# MicroWordClock2.net
KiCad netlist of a schematic drawn in EAGLE
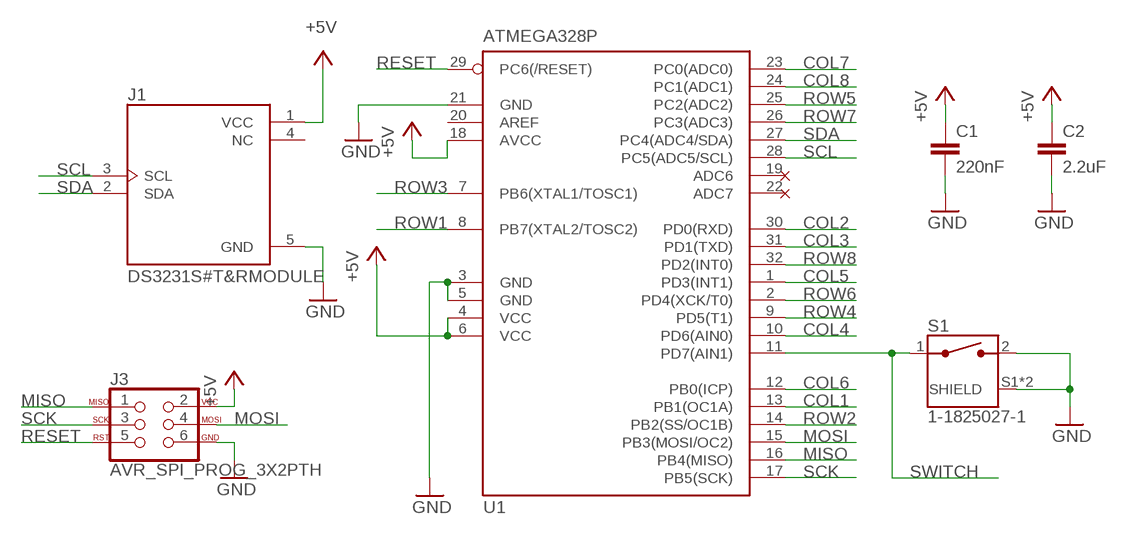
[diagram p0: schematic, sheet 1]
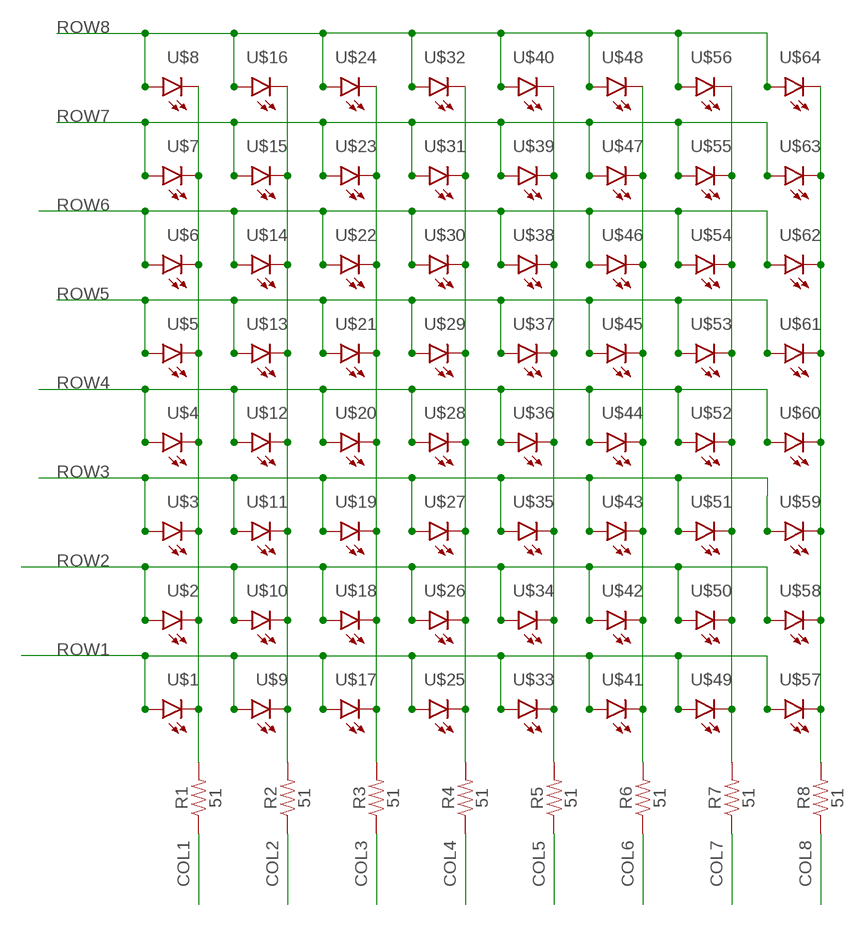
[diagram p1: schematic, sheet 2]
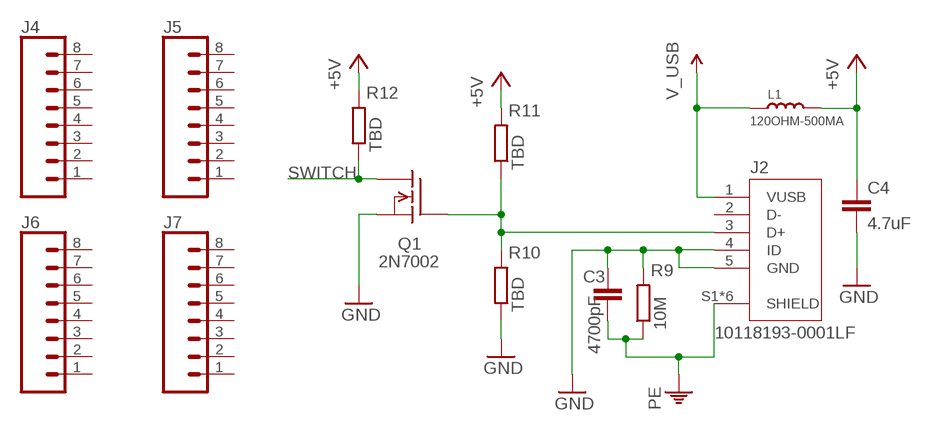
[diagram p2: schematic, sheet 3]

(export (version "E")
  (design (tool "Eeschema 10.0.6"))
  (components
    (comp (ref "R1")
      (value "51")
      (footprint "eagle-import:0603")
      (libsource (lib "eagle-import") (part "470OHM-0603-1/10W-1%"))
    )
    (comp (ref "R2")
      (value "51")
      (footprint "eagle-import:0603")
      (libsource (lib "eagle-import") (part "470OHM-0603-1/10W-1%"))
    )
    (comp (ref "R3")
      (value "51")
      (footprint "eagle-import:0603")
      (libsource (lib "eagle-import") (part "470OHM-0603-1/10W-1%"))
    )
    (comp (ref "R4")
      (value "51")
      (footprint "eagle-import:0603")
      (libsource (lib "eagle-import") (part "470OHM-0603-1/10W-1%"))
    )
    (comp (ref "R5")
      (value "51")
      (footprint "eagle-import:0603")
      (libsource (lib "eagle-import") (part "470OHM-0603-1/10W-1%"))
    )
    (comp (ref "R6")
      (value "51")
      (footprint "eagle-import:0603")
      (libsource (lib "eagle-import") (part "470OHM-0603-1/10W-1%"))
    )
    (comp (ref "R7")
      (value "51")
      (footprint "eagle-import:0603")
      (libsource (lib "eagle-import") (part "470OHM-0603-1/10W-1%"))
    )
    (comp (ref "R8")
      (value "51")
      (footprint "eagle-import:0603")
      (libsource (lib "eagle-import") (part "470OHM-0603-1/10W-1%"))
    )
    (comp (ref "U$1")
      (value "WHITE")
      (footprint "eagle-import:1113(2835METRIC)")
      (libsource (lib "eagle-import") (part "JE2835AWT-00-0000-0B0A0BG840E"))
    )
    (comp (ref "U$2")
      (value "WHITE")
      (footprint "eagle-import:1113(2835METRIC)")
      (libsource (lib "eagle-import") (part "JE2835AWT-00-0000-0B0A0BG840E"))
    )
    (comp (ref "U$3")
      (value "WHITE")
      (footprint "eagle-import:1113(2835METRIC)")
      (libsource (lib "eagle-import") (part "JE2835AWT-00-0000-0B0A0BG840E"))
    )
    (comp (ref "U$4")
      (value "WHITE")
      (footprint "eagle-import:1113(2835METRIC)")
      (libsource (lib "eagle-import") (part "JE2835AWT-00-0000-0B0A0BG840E"))
    )
    (comp (ref "U$5")
      (value "WHITE")
      (footprint "eagle-import:1113(2835METRIC)")
      (libsource (lib "eagle-import") (part "JE2835AWT-00-0000-0B0A0BG840E"))
    )
    (comp (ref "U$6")
      (value "WHITE")
      (footprint "eagle-import:1113(2835METRIC)")
      (libsource (lib "eagle-import") (part "JE2835AWT-00-0000-0B0A0BG840E"))
    )
    (comp (ref "U$7")
      (value "WHITE")
      (footprint "eagle-import:1113(2835METRIC)")
      (libsource (lib "eagle-import") (part "JE2835AWT-00-0000-0B0A0BG840E"))
    )
    (comp (ref "U$8")
      (value "WHITE")
      (footprint "eagle-import:1113(2835METRIC)")
      (libsource (lib "eagle-import") (part "JE2835AWT-00-0000-0B0A0BG840E"))
    )
    (comp (ref "U$9")
      (value "WHITE")
      (footprint "eagle-import:1113(2835METRIC)")
      (libsource (lib "eagle-import") (part "JE2835AWT-00-0000-0B0A0BG840E"))
    )
    (comp (ref "U$10")
      (value "WHITE")
      (footprint "eagle-import:1113(2835METRIC)")
      (libsource (lib "eagle-import") (part "JE2835AWT-00-0000-0B0A0BG840E"))
    )
    (comp (ref "U$11")
      (value "WHITE")
      (footprint "eagle-import:1113(2835METRIC)")
      (libsource (lib "eagle-import") (part "JE2835AWT-00-0000-0B0A0BG840E"))
    )
    (comp (ref "U$12")
      (value "WHITE")
      (footprint "eagle-import:1113(2835METRIC)")
      (libsource (lib "eagle-import") (part "JE2835AWT-00-0000-0B0A0BG840E"))
    )
    (comp (ref "U$13")
      (value "WHITE")
      (footprint "eagle-import:1113(2835METRIC)")
      (libsource (lib "eagle-import") (part "JE2835AWT-00-0000-0B0A0BG840E"))
    )
    (comp (ref "U$14")
      (value "WHITE")
      (footprint "eagle-import:1113(2835METRIC)")
      (libsource (lib "eagle-import") (part "JE2835AWT-00-0000-0B0A0BG840E"))
    )
    (comp (ref "U$15")
      (value "WHITE")
      (footprint "eagle-import:1113(2835METRIC)")
      (libsource (lib "eagle-import") (part "JE2835AWT-00-0000-0B0A0BG840E"))
    )
    (comp (ref "U$16")
      (value "WHITE")
      (footprint "eagle-import:1113(2835METRIC)")
      (libsource (lib "eagle-import") (part "JE2835AWT-00-0000-0B0A0BG840E"))
    )
    (comp (ref "U$17")
      (value "WHITE")
      (footprint "eagle-import:1113(2835METRIC)")
      (libsource (lib "eagle-import") (part "JE2835AWT-00-0000-0B0A0BG840E"))
    )
    (comp (ref "U$18")
      (value "WHITE")
      (footprint "eagle-import:1113(2835METRIC)")
      (libsource (lib "eagle-import") (part "JE2835AWT-00-0000-0B0A0BG840E"))
    )
    (comp (ref "U$19")
      (value "WHITE")
      (footprint "eagle-import:1113(2835METRIC)")
      (libsource (lib "eagle-import") (part "JE2835AWT-00-0000-0B0A0BG840E"))
    )
    (comp (ref "U$20")
      (value "WHITE")
      (footprint "eagle-import:1113(2835METRIC)")
      (libsource (lib "eagle-import") (part "JE2835AWT-00-0000-0B0A0BG840E"))
    )
    (comp (ref "U$21")
      (value "WHITE")
      (footprint "eagle-import:1113(2835METRIC)")
      (libsource (lib "eagle-import") (part "JE2835AWT-00-0000-0B0A0BG840E"))
    )
    (comp (ref "U$22")
      (value "WHITE")
      (footprint "eagle-import:1113(2835METRIC)")
      (libsource (lib "eagle-import") (part "JE2835AWT-00-0000-0B0A0BG840E"))
    )
    (comp (ref "U$23")
      (value "WHITE")
      (footprint "eagle-import:1113(2835METRIC)")
      (libsource (lib "eagle-import") (part "JE2835AWT-00-0000-0B0A0BG840E"))
    )
    (comp (ref "U$24")
      (value "WHITE")
      (footprint "eagle-import:1113(2835METRIC)")
      (libsource (lib "eagle-import") (part "JE2835AWT-00-0000-0B0A0BG840E"))
    )
    (comp (ref "U$25")
      (value "WHITE")
      (footprint "eagle-import:1113(2835METRIC)")
      (libsource (lib "eagle-import") (part "JE2835AWT-00-0000-0B0A0BG840E"))
    )
    (comp (ref "U$26")
      (value "WHITE")
      (footprint "eagle-import:1113(2835METRIC)")
      (libsource (lib "eagle-import") (part "JE2835AWT-00-0000-0B0A0BG840E"))
    )
    (comp (ref "U$27")
      (value "WHITE")
      (footprint "eagle-import:1113(2835METRIC)")
      (libsource (lib "eagle-import") (part "JE2835AWT-00-0000-0B0A0BG840E"))
    )
    (comp (ref "U$28")
      (value "WHITE")
      (footprint "eagle-import:1113(2835METRIC)")
      (libsource (lib "eagle-import") (part "JE2835AWT-00-0000-0B0A0BG840E"))
    )
    (comp (ref "U$29")
      (value "WHITE")
      (footprint "eagle-import:1113(2835METRIC)")
      (libsource (lib "eagle-import") (part "JE2835AWT-00-0000-0B0A0BG840E"))
    )
    (comp (ref "U$30")
      (value "WHITE")
      (footprint "eagle-import:1113(2835METRIC)")
      (libsource (lib "eagle-import") (part "JE2835AWT-00-0000-0B0A0BG840E"))
    )
    (comp (ref "U$31")
      (value "WHITE")
      (footprint "eagle-import:1113(2835METRIC)")
      (libsource (lib "eagle-import") (part "JE2835AWT-00-0000-0B0A0BG840E"))
    )
    (comp (ref "U$32")
      (value "WHITE")
      (footprint "eagle-import:1113(2835METRIC)")
      (libsource (lib "eagle-import") (part "JE2835AWT-00-0000-0B0A0BG840E"))
    )
    (comp (ref "U$33")
      (value "WHITE")
      (footprint "eagle-import:1113(2835METRIC)")
      (libsource (lib "eagle-import") (part "JE2835AWT-00-0000-0B0A0BG840E"))
    )
    (comp (ref "U$34")
      (value "WHITE")
      (footprint "eagle-import:1113(2835METRIC)")
      (libsource (lib "eagle-import") (part "JE2835AWT-00-0000-0B0A0BG840E"))
    )
    (comp (ref "U$35")
      (value "WHITE")
      (footprint "eagle-import:1113(2835METRIC)")
      (libsource (lib "eagle-import") (part "JE2835AWT-00-0000-0B0A0BG840E"))
    )
    (comp (ref "U$36")
      (value "WHITE")
      (footprint "eagle-import:1113(2835METRIC)")
      (libsource (lib "eagle-import") (part "JE2835AWT-00-0000-0B0A0BG840E"))
    )
    (comp (ref "U$37")
      (value "WHITE")
      (footprint "eagle-import:1113(2835METRIC)")
      (libsource (lib "eagle-import") (part "JE2835AWT-00-0000-0B0A0BG840E"))
    )
    (comp (ref "U$38")
      (value "WHITE")
      (footprint "eagle-import:1113(2835METRIC)")
      (libsource (lib "eagle-import") (part "JE2835AWT-00-0000-0B0A0BG840E"))
    )
    (comp (ref "U$39")
      (value "WHITE")
      (footprint "eagle-import:1113(2835METRIC)")
      (libsource (lib "eagle-import") (part "JE2835AWT-00-0000-0B0A0BG840E"))
    )
    (comp (ref "U$40")
      (value "WHITE")
      (footprint "eagle-import:1113(2835METRIC)")
      (libsource (lib "eagle-import") (part "JE2835AWT-00-0000-0B0A0BG840E"))
    )
    (comp (ref "U$41")
      (value "WHITE")
      (footprint "eagle-import:1113(2835METRIC)")
      (libsource (lib "eagle-import") (part "JE2835AWT-00-0000-0B0A0BG840E"))
    )
    (comp (ref "U$42")
      (value "WHITE")
      (footprint "eagle-import:1113(2835METRIC)")
      (libsource (lib "eagle-import") (part "JE2835AWT-00-0000-0B0A0BG840E"))
    )
    (comp (ref "U$43")
      (value "WHITE")
      (footprint "eagle-import:1113(2835METRIC)")
      (libsource (lib "eagle-import") (part "JE2835AWT-00-0000-0B0A0BG840E"))
    )
    (comp (ref "U$44")
      (value "WHITE")
      (footprint "eagle-import:1113(2835METRIC)")
      (libsource (lib "eagle-import") (part "JE2835AWT-00-0000-0B0A0BG840E"))
    )
    (comp (ref "U$45")
      (value "WHITE")
      (footprint "eagle-import:1113(2835METRIC)")
      (libsource (lib "eagle-import") (part "JE2835AWT-00-0000-0B0A0BG840E"))
    )
    (comp (ref "U$46")
      (value "WHITE")
      (footprint "eagle-import:1113(2835METRIC)")
      (libsource (lib "eagle-import") (part "JE2835AWT-00-0000-0B0A0BG840E"))
    )
    (comp (ref "U$47")
      (value "WHITE")
      (footprint "eagle-import:1113(2835METRIC)")
      (libsource (lib "eagle-import") (part "JE2835AWT-00-0000-0B0A0BG840E"))
    )
    (comp (ref "U$48")
      (value "WHITE")
      (footprint "eagle-import:1113(2835METRIC)")
      (libsource (lib "eagle-import") (part "JE2835AWT-00-0000-0B0A0BG840E"))
    )
    (comp (ref "U$49")
      (value "WHITE")
      (footprint "eagle-import:1113(2835METRIC)")
      (libsource (lib "eagle-import") (part "JE2835AWT-00-0000-0B0A0BG840E"))
    )
    (comp (ref "U$50")
      (value "WHITE")
      (footprint "eagle-import:1113(2835METRIC)")
      (libsource (lib "eagle-import") (part "JE2835AWT-00-0000-0B0A0BG840E"))
    )
    (comp (ref "U$51")
      (value "WHITE")
      (footprint "eagle-import:1113(2835METRIC)")
      (libsource (lib "eagle-import") (part "JE2835AWT-00-0000-0B0A0BG840E"))
    )
    (comp (ref "U$52")
      (value "WHITE")
      (footprint "eagle-import:1113(2835METRIC)")
      (libsource (lib "eagle-import") (part "JE2835AWT-00-0000-0B0A0BG840E"))
    )
    (comp (ref "U$53")
      (value "WHITE")
      (footprint "eagle-import:1113(2835METRIC)")
      (libsource (lib "eagle-import") (part "JE2835AWT-00-0000-0B0A0BG840E"))
    )
    (comp (ref "U$54")
      (value "WHITE")
      (footprint "eagle-import:1113(2835METRIC)")
      (libsource (lib "eagle-import") (part "JE2835AWT-00-0000-0B0A0BG840E"))
    )
    (comp (ref "U$55")
      (value "WHITE")
      (footprint "eagle-import:1113(2835METRIC)")
      (libsource (lib "eagle-import") (part "JE2835AWT-00-0000-0B0A0BG840E"))
    )
    (comp (ref "U$56")
      (value "WHITE")
      (footprint "eagle-import:1113(2835METRIC)")
      (libsource (lib "eagle-import") (part "JE2835AWT-00-0000-0B0A0BG840E"))
    )
    (comp (ref "U$57")
      (value "WHITE")
      (footprint "eagle-import:1113(2835METRIC)")
      (libsource (lib "eagle-import") (part "JE2835AWT-00-0000-0B0A0BG840E"))
    )
    (comp (ref "U$58")
      (value "WHITE")
      (footprint "eagle-import:1113(2835METRIC)")
      (libsource (lib "eagle-import") (part "JE2835AWT-00-0000-0B0A0BG840E"))
    )
    (comp (ref "U$59")
      (value "WHITE")
      (footprint "eagle-import:1113(2835METRIC)")
      (libsource (lib "eagle-import") (part "JE2835AWT-00-0000-0B0A0BG840E"))
    )
    (comp (ref "U$60")
      (value "WHITE")
      (footprint "eagle-import:1113(2835METRIC)")
      (libsource (lib "eagle-import") (part "JE2835AWT-00-0000-0B0A0BG840E"))
    )
    (comp (ref "U$61")
      (value "WHITE")
      (footprint "eagle-import:1113(2835METRIC)")
      (libsource (lib "eagle-import") (part "JE2835AWT-00-0000-0B0A0BG840E"))
    )
    (comp (ref "U$62")
      (value "WHITE")
      (footprint "eagle-import:1113(2835METRIC)")
      (libsource (lib "eagle-import") (part "JE2835AWT-00-0000-0B0A0BG840E"))
    )
    (comp (ref "U$63")
      (value "WHITE")
      (footprint "eagle-import:1113(2835METRIC)")
      (libsource (lib "eagle-import") (part "JE2835AWT-00-0000-0B0A0BG840E"))
    )
    (comp (ref "U$64")
      (value "WHITE")
      (footprint "eagle-import:1113(2835METRIC)")
      (libsource (lib "eagle-import") (part "JE2835AWT-00-0000-0B0A0BG840E"))
    )
    (comp (ref "C3")
      (value "4700pF")
      (footprint "eagle-import:C0603")
      (libsource (lib "eagle-import") (part "C-EUC0603"))
    )
    (comp (ref "C4")
      (value "4.7uF")
      (footprint "eagle-import:C0603")
      (libsource (lib "eagle-import") (part "C-EUC0603"))
    )
    (comp (ref "J2")
      (value "10118193-0001LF")
      (footprint "eagle-import:FCI_10118193-0001LF")
      (fields (field (name "DIGI-KEY_PART_NUMBER") "609-4616-1-ND") (field (name "MF") "Amphenol ICC"))
      (libsource (lib "eagle-import") (part "10118193-0001LF"))
    )
    (comp (ref "J4")
      (value "CONN_08\"")
      (footprint "eagle-import:1X08")
      (libsource (lib "eagle-import") (part "CONN_08{dblquote}"))
    )
    (comp (ref "J5")
      (value "CONN_08\"")
      (footprint "eagle-import:1X08")
      (libsource (lib "eagle-import") (part "CONN_08{dblquote}"))
    )
    (comp (ref "J6")
      (value "CONN_08\"")
      (footprint "eagle-import:1X08")
      (libsource (lib "eagle-import") (part "CONN_08{dblquote}"))
    )
    (comp (ref "J7")
      (value "CONN_08\"")
      (footprint "eagle-import:1X08")
      (libsource (lib "eagle-import") (part "CONN_08{dblquote}"))
    )
    (comp (ref "L1")
      (value "120OHM-500MA")
      (footprint "eagle-import:L0603")
      (fields (field (name "MPN") "BLM18AG121SN1D"))
      (libsource (lib "eagle-import") (part "SMD-FERRITE-CHIP-120-OHM-500MA(0603)"))
    )
    (comp (ref "Q1")
      (value "2N7002")
      (footprint "eagle-import:SOT23")
      (fields (field (name "MF") "STMicroelectronics"))
      (libsource (lib "eagle-import") (part "2N7002"))
    )
    (comp (ref "R9")
      (value "10M")
      (footprint "eagle-import:R0603")
      (libsource (lib "eagle-import") (part "R-EU_R0603"))
    )
    (comp (ref "R10")
      (value "TBD")
      (footprint "eagle-import:R0603")
      (libsource (lib "eagle-import") (part "R-EU_R0603"))
    )
    (comp (ref "R11")
      (value "TBD")
      (footprint "eagle-import:R0603")
      (libsource (lib "eagle-import") (part "R-EU_R0603"))
    )
    (comp (ref "R12")
      (value "TBD")
      (footprint "eagle-import:R0603")
      (libsource (lib "eagle-import") (part "R-EU_R0603"))
    )
    (comp (ref "C1")
      (value "220nF")
      (footprint "eagle-import:C0603")
      (libsource (lib "eagle-import") (part "C-EUC0603"))
    )
    (comp (ref "C2")
      (value "2.2uF")
      (footprint "eagle-import:C0603")
      (libsource (lib "eagle-import") (part "C-EUC0603"))
    )
    (comp (ref "J1")
      (value "DS3231S#T&RMODULE")
      (footprint "eagle-import:1X05")
      (libsource (lib "eagle-import") (part "DS3231S#T&RMODULE"))
    )
    (comp (ref "J3")
      (value "AVR_SPI_PROG_3X2PTH")
      (footprint "eagle-import:2X3")
      (libsource (lib "eagle-import") (part "AVR_SPI_PROG_3X2PTH"))
    )
    (comp (ref "S1")
      (value "1-1825027-1")
      (footprint "eagle-import:SW_1-1825027-1")
      (fields (field (name "DIGI-KEY_PART_NUMBER") "450-1658-ND") (field (name "MF") "TE Connectivity"))
      (libsource (lib "eagle-import") (part "1-1825027-1"))
    )
    (comp (ref "U1")
      (value "ATMEGA328P")
      (footprint "eagle-import:TQFP32-08")
      (fields (field (name "MPN") "ATMEGA8-16AU"))
      (libsource (lib "eagle-import") (part "MEGA8-AI"))
    )
  )
  (nets
    (net (code "1") (name "+5V") (class "Default")
      (node (ref "C1") (pin "1") (pinfunction "1_1") (pintype "passive"))
      (node (ref "C2") (pin "1") (pinfunction "1_1") (pintype "passive"))
      (node (ref "C4") (pin "1") (pinfunction "1_1") (pintype "passive"))
      (node (ref "J1") (pin "1") (pinfunction "VCC_1") (pintype "power_in"))
      (node (ref "J3") (pin "2") (pinfunction "2_2") (pintype "passive"))
      (node (ref "L1") (pin "2") (pinfunction "2_2") (pintype "passive"))
      (node (ref "R11") (pin "2") (pinfunction "2_2") (pintype "passive"))
      (node (ref "R12") (pin "2") (pinfunction "2_2") (pintype "passive"))
      (node (ref "U1") (pin "18") (pinfunction "AVCC_18") (pintype "power_in"))
      (node (ref "U1") (pin "4") (pinfunction "VCC_4") (pintype "power_in"))
      (node (ref "U1") (pin "6") (pinfunction "VCC_6") (pintype "power_in"))
    )
    (net (code "2") (name "COL1") (class "Default")
      (node (ref "R1") (pin "1") (pinfunction "1_1") (pintype "passive"))
      (node (ref "U1") (pin "13") (pinfunction "PB1(OC1A)_13") (pintype "bidirectional"))
    )
    (net (code "3") (name "COL2") (class "Default")
      (node (ref "R2") (pin "1") (pinfunction "1_1") (pintype "passive"))
      (node (ref "U1") (pin "30") (pinfunction "PD0(RXD)_30") (pintype "bidirectional"))
    )
    (net (code "4") (name "COL3") (class "Default")
      (node (ref "R3") (pin "1") (pinfunction "1_1") (pintype "passive"))
      (node (ref "U1") (pin "31") (pinfunction "PD1(TXD)_31") (pintype "bidirectional"))
    )
    (net (code "5") (name "COL4") (class "Default")
      (node (ref "R4") (pin "1") (pinfunction "1_1") (pintype "passive"))
      (node (ref "U1") (pin "10") (pinfunction "PD6(AIN0)_10") (pintype "bidirectional"))
    )
    (net (code "6") (name "COL5") (class "Default")
      (node (ref "R5") (pin "1") (pinfunction "1_1") (pintype "passive"))
      (node (ref "U1") (pin "1") (pinfunction "PD3(INT1)_1") (pintype "bidirectional"))
    )
    (net (code "7") (name "COL6") (class "Default")
      (node (ref "R6") (pin "1") (pinfunction "1_1") (pintype "passive"))
      (node (ref "U1") (pin "12") (pinfunction "PB0(ICP)_12") (pintype "bidirectional"))
    )
    (net (code "8") (name "COL7") (class "Default")
      (node (ref "R7") (pin "1") (pinfunction "1_1") (pintype "passive"))
      (node (ref "U1") (pin "23") (pinfunction "PC0(ADC0)_23") (pintype "bidirectional"))
    )
    (net (code "9") (name "COL8") (class "Default")
      (node (ref "R8") (pin "1") (pinfunction "1_1") (pintype "passive"))
      (node (ref "U1") (pin "24") (pinfunction "PC1(ADC1)_24") (pintype "bidirectional"))
    )
    (net (code "10") (name "GND") (class "Default")
      (node (ref "C1") (pin "2") (pinfunction "2_2") (pintype "passive"))
      (node (ref "C2") (pin "2") (pinfunction "2_2") (pintype "passive"))
      (node (ref "C3") (pin "1") (pinfunction "1_1") (pintype "passive"))
      (node (ref "C4") (pin "2") (pinfunction "2_2") (pintype "passive"))
      (node (ref "J1") (pin "5") (pinfunction "GND_5") (pintype "power_in"))
      (node (ref "J2") (pin "4") (pinfunction "ID_4") (pintype "passive"))
      (node (ref "J2") (pin "5") (pinfunction "GND_5") (pintype "passive"))
      (node (ref "J3") (pin "6") (pinfunction "6_6") (pintype "passive"))
      (node (ref "Q1") (pin "2") (pinfunction "S_2") (pintype "passive"))
      (node (ref "R10") (pin "1") (pinfunction "1_1") (pintype "passive"))
      (node (ref "R9") (pin "2") (pinfunction "2_2") (pintype "passive"))
      (node (ref "S1") (pin "2") (pinfunction "2_2") (pintype "passive"))
      (node (ref "S1") (pin "S1") (pinfunction "SHIELD_S1") (pintype "power_in"))
      (node (ref "S1") (pin "S2") (pinfunction "SHIELD_S2") (pintype "power_in"))
      (node (ref "U1") (pin "21") (pinfunction "GND_21") (pintype "power_in"))
      (node (ref "U1") (pin "3") (pinfunction "GND_3") (pintype "power_in"))
      (node (ref "U1") (pin "5") (pinfunction "GND_5") (pintype "power_in"))
    )
    (net (code "11") (name "MISO") (class "Default")
      (node (ref "J3") (pin "1") (pinfunction "1_1") (pintype "passive"))
      (node (ref "U1") (pin "16") (pinfunction "PB4(MISO)_16") (pintype "bidirectional"))
    )
    (net (code "12") (name "MOSI") (class "Default")
      (node (ref "J3") (pin "4") (pinfunction "4_4") (pintype "passive"))
      (node (ref "U1") (pin "15") (pinfunction "PB3(MOSI/OC2)_15") (pintype "bidirectional"))
    )
    (net (code "13") (name "Net-(J2-D+)") (class "Default")
      (node (ref "J2") (pin "3") (pinfunction "D+_3") (pintype "passive"))
      (node (ref "Q1") (pin "1") (pinfunction "G_1") (pintype "passive"))
      (node (ref "R10") (pin "2") (pinfunction "2_2") (pintype "passive"))
      (node (ref "R11") (pin "1") (pinfunction "1_1") (pintype "passive"))
    )
    (net (code "14") (name "Net-(U$1-C)") (class "Default")
      (node (ref "R1") (pin "2") (pinfunction "2_2") (pintype "passive"))
      (node (ref "U$1") (pin "CATHODE") (pinfunction "C_CATHODE") (pintype "passive"))
      (node (ref "U$2") (pin "CATHODE") (pinfunction "C_CATHODE") (pintype "passive"))
      (node (ref "U$3") (pin "CATHODE") (pinfunction "C_CATHODE") (pintype "passive"))
      (node (ref "U$4") (pin "CATHODE") (pinfunction "C_CATHODE") (pintype "passive"))
      (node (ref "U$5") (pin "CATHODE") (pinfunction "C_CATHODE") (pintype "passive"))
      (node (ref "U$6") (pin "CATHODE") (pinfunction "C_CATHODE") (pintype "passive"))
      (node (ref "U$7") (pin "CATHODE") (pinfunction "C_CATHODE") (pintype "passive"))
      (node (ref "U$8") (pin "CATHODE") (pinfunction "C_CATHODE") (pintype "passive"))
    )
    (net (code "15") (name "Net-(U$10-C)") (class "Default")
      (node (ref "R2") (pin "2") (pinfunction "2_2") (pintype "passive"))
      (node (ref "U$10") (pin "CATHODE") (pinfunction "C_CATHODE") (pintype "passive"))
      (node (ref "U$11") (pin "CATHODE") (pinfunction "C_CATHODE") (pintype "passive"))
      (node (ref "U$12") (pin "CATHODE") (pinfunction "C_CATHODE") (pintype "passive"))
      (node (ref "U$13") (pin "CATHODE") (pinfunction "C_CATHODE") (pintype "passive"))
      (node (ref "U$14") (pin "CATHODE") (pinfunction "C_CATHODE") (pintype "passive"))
      (node (ref "U$15") (pin "CATHODE") (pinfunction "C_CATHODE") (pintype "passive"))
      (node (ref "U$16") (pin "CATHODE") (pinfunction "C_CATHODE") (pintype "passive"))
      (node (ref "U$9") (pin "CATHODE") (pinfunction "C_CATHODE") (pintype "passive"))
    )
    (net (code "16") (name "Net-(U$17-C)") (class "Default")
      (node (ref "R3") (pin "2") (pinfunction "2_2") (pintype "passive"))
      (node (ref "U$17") (pin "CATHODE") (pinfunction "C_CATHODE") (pintype "passive"))
      (node (ref "U$18") (pin "CATHODE") (pinfunction "C_CATHODE") (pintype "passive"))
      (node (ref "U$19") (pin "CATHODE") (pinfunction "C_CATHODE") (pintype "passive"))
      (node (ref "U$20") (pin "CATHODE") (pinfunction "C_CATHODE") (pintype "passive"))
      (node (ref "U$21") (pin "CATHODE") (pinfunction "C_CATHODE") (pintype "passive"))
      (node (ref "U$22") (pin "CATHODE") (pinfunction "C_CATHODE") (pintype "passive"))
      (node (ref "U$23") (pin "CATHODE") (pinfunction "C_CATHODE") (pintype "passive"))
      (node (ref "U$24") (pin "CATHODE") (pinfunction "C_CATHODE") (pintype "passive"))
    )
    (net (code "17") (name "Net-(U$25-C)") (class "Default")
      (node (ref "R4") (pin "2") (pinfunction "2_2") (pintype "passive"))
      (node (ref "U$25") (pin "CATHODE") (pinfunction "C_CATHODE") (pintype "passive"))
      (node (ref "U$26") (pin "CATHODE") (pinfunction "C_CATHODE") (pintype "passive"))
      (node (ref "U$27") (pin "CATHODE") (pinfunction "C_CATHODE") (pintype "passive"))
      (node (ref "U$28") (pin "CATHODE") (pinfunction "C_CATHODE") (pintype "passive"))
      (node (ref "U$29") (pin "CATHODE") (pinfunction "C_CATHODE") (pintype "passive"))
      (node (ref "U$30") (pin "CATHODE") (pinfunction "C_CATHODE") (pintype "passive"))
      (node (ref "U$31") (pin "CATHODE") (pinfunction "C_CATHODE") (pintype "passive"))
      (node (ref "U$32") (pin "CATHODE") (pinfunction "C_CATHODE") (pintype "passive"))
    )
    (net (code "18") (name "Net-(U$33-C)") (class "Default")
      (node (ref "R5") (pin "2") (pinfunction "2_2") (pintype "passive"))
      (node (ref "U$33") (pin "CATHODE") (pinfunction "C_CATHODE") (pintype "passive"))
      (node (ref "U$34") (pin "CATHODE") (pinfunction "C_CATHODE") (pintype "passive"))
      (node (ref "U$35") (pin "CATHODE") (pinfunction "C_CATHODE") (pintype "passive"))
      (node (ref "U$36") (pin "CATHODE") (pinfunction "C_CATHODE") (pintype "passive"))
      (node (ref "U$37") (pin "CATHODE") (pinfunction "C_CATHODE") (pintype "passive"))
      (node (ref "U$38") (pin "CATHODE") (pinfunction "C_CATHODE") (pintype "passive"))
      (node (ref "U$39") (pin "CATHODE") (pinfunction "C_CATHODE") (pintype "passive"))
      (node (ref "U$40") (pin "CATHODE") (pinfunction "C_CATHODE") (pintype "passive"))
    )
    (net (code "19") (name "Net-(U$41-C)") (class "Default")
      (node (ref "R6") (pin "2") (pinfunction "2_2") (pintype "passive"))
      (node (ref "U$41") (pin "CATHODE") (pinfunction "C_CATHODE") (pintype "passive"))
      (node (ref "U$42") (pin "CATHODE") (pinfunction "C_CATHODE") (pintype "passive"))
      (node (ref "U$43") (pin "CATHODE") (pinfunction "C_CATHODE") (pintype "passive"))
      (node (ref "U$44") (pin "CATHODE") (pinfunction "C_CATHODE") (pintype "passive"))
      (node (ref "U$45") (pin "CATHODE") (pinfunction "C_CATHODE") (pintype "passive"))
      (node (ref "U$46") (pin "CATHODE") (pinfunction "C_CATHODE") (pintype "passive"))
      (node (ref "U$47") (pin "CATHODE") (pinfunction "C_CATHODE") (pintype "passive"))
      (node (ref "U$48") (pin "CATHODE") (pinfunction "C_CATHODE") (pintype "passive"))
    )
    (net (code "20") (name "Net-(U$49-C)") (class "Default")
      (node (ref "R7") (pin "2") (pinfunction "2_2") (pintype "passive"))
      (node (ref "U$49") (pin "CATHODE") (pinfunction "C_CATHODE") (pintype "passive"))
      (node (ref "U$50") (pin "CATHODE") (pinfunction "C_CATHODE") (pintype "passive"))
      (node (ref "U$51") (pin "CATHODE") (pinfunction "C_CATHODE") (pintype "passive"))
      (node (ref "U$52") (pin "CATHODE") (pinfunction "C_CATHODE") (pintype "passive"))
      (node (ref "U$53") (pin "CATHODE") (pinfunction "C_CATHODE") (pintype "passive"))
      (node (ref "U$54") (pin "CATHODE") (pinfunction "C_CATHODE") (pintype "passive"))
      (node (ref "U$55") (pin "CATHODE") (pinfunction "C_CATHODE") (pintype "passive"))
      (node (ref "U$56") (pin "CATHODE") (pinfunction "C_CATHODE") (pintype "passive"))
    )
    (net (code "21") (name "Net-(U$57-C)") (class "Default")
      (node (ref "R8") (pin "2") (pinfunction "2_2") (pintype "passive"))
      (node (ref "U$57") (pin "CATHODE") (pinfunction "C_CATHODE") (pintype "passive"))
      (node (ref "U$58") (pin "CATHODE") (pinfunction "C_CATHODE") (pintype "passive"))
      (node (ref "U$59") (pin "CATHODE") (pinfunction "C_CATHODE") (pintype "passive"))
      (node (ref "U$60") (pin "CATHODE") (pinfunction "C_CATHODE") (pintype "passive"))
      (node (ref "U$61") (pin "CATHODE") (pinfunction "C_CATHODE") (pintype "passive"))
      (node (ref "U$62") (pin "CATHODE") (pinfunction "C_CATHODE") (pintype "passive"))
      (node (ref "U$63") (pin "CATHODE") (pinfunction "C_CATHODE") (pintype "passive"))
      (node (ref "U$64") (pin "CATHODE") (pinfunction "C_CATHODE") (pintype "passive"))
    )
    (net (code "22") (name "PE") (class "Default")
      (node (ref "C3") (pin "2") (pinfunction "2_2") (pintype "passive"))
      (node (ref "J2") (pin "S1") (pinfunction "SHIELD_S1") (pintype "passive"))
      (node (ref "J2") (pin "S2") (pinfunction "SHIELD_S2") (pintype "passive"))
      (node (ref "J2") (pin "S3") (pinfunction "SHIELD_S3") (pintype "passive"))
      (node (ref "J2") (pin "S4") (pinfunction "SHIELD_S4") (pintype "passive"))
      (node (ref "J2") (pin "S5") (pinfunction "SHIELD_S5") (pintype "passive"))
      (node (ref "J2") (pin "S6") (pinfunction "SHIELD_S6") (pintype "passive"))
      (node (ref "R9") (pin "1") (pinfunction "1_1") (pintype "passive"))
    )
    (net (code "23") (name "RESET") (class "Default")
      (node (ref "J3") (pin "5") (pinfunction "5_5") (pintype "passive"))
      (node (ref "U1") (pin "29") (pinfunction "PC6(/RESET)_29") (pintype "bidirectional"))
    )
    (net (code "24") (name "ROW1") (class "Default")
      (node (ref "U$1") (pin "ANODE") (pinfunction "A_ANODE") (pintype "passive"))
      (node (ref "U$17") (pin "ANODE") (pinfunction "A_ANODE") (pintype "passive"))
      (node (ref "U$25") (pin "ANODE") (pinfunction "A_ANODE") (pintype "passive"))
      (node (ref "U$33") (pin "ANODE") (pinfunction "A_ANODE") (pintype "passive"))
      (node (ref "U$41") (pin "ANODE") (pinfunction "A_ANODE") (pintype "passive"))
      (node (ref "U$49") (pin "ANODE") (pinfunction "A_ANODE") (pintype "passive"))
      (node (ref "U$57") (pin "ANODE") (pinfunction "A_ANODE") (pintype "passive"))
      (node (ref "U$9") (pin "ANODE") (pinfunction "A_ANODE") (pintype "passive"))
      (node (ref "U1") (pin "8") (pinfunction "PB7(XTAL2/TOSC2)_8") (pintype "bidirectional"))
    )
    (net (code "25") (name "ROW2") (class "Default")
      (node (ref "U$10") (pin "ANODE") (pinfunction "A_ANODE") (pintype "passive"))
      (node (ref "U$18") (pin "ANODE") (pinfunction "A_ANODE") (pintype "passive"))
      (node (ref "U$2") (pin "ANODE") (pinfunction "A_ANODE") (pintype "passive"))
      (node (ref "U$26") (pin "ANODE") (pinfunction "A_ANODE") (pintype "passive"))
      (node (ref "U$34") (pin "ANODE") (pinfunction "A_ANODE") (pintype "passive"))
      (node (ref "U$42") (pin "ANODE") (pinfunction "A_ANODE") (pintype "passive"))
      (node (ref "U$50") (pin "ANODE") (pinfunction "A_ANODE") (pintype "passive"))
      (node (ref "U$58") (pin "ANODE") (pinfunction "A_ANODE") (pintype "passive"))
      (node (ref "U1") (pin "14") (pinfunction "PB2(SS/OC1B)_14") (pintype "bidirectional"))
    )
    (net (code "26") (name "ROW3") (class "Default")
      (node (ref "U$11") (pin "ANODE") (pinfunction "A_ANODE") (pintype "passive"))
      (node (ref "U$19") (pin "ANODE") (pinfunction "A_ANODE") (pintype "passive"))
      (node (ref "U$27") (pin "ANODE") (pinfunction "A_ANODE") (pintype "passive"))
      (node (ref "U$3") (pin "ANODE") (pinfunction "A_ANODE") (pintype "passive"))
      (node (ref "U$35") (pin "ANODE") (pinfunction "A_ANODE") (pintype "passive"))
      (node (ref "U$43") (pin "ANODE") (pinfunction "A_ANODE") (pintype "passive"))
      (node (ref "U$51") (pin "ANODE") (pinfunction "A_ANODE") (pintype "passive"))
      (node (ref "U$59") (pin "ANODE") (pinfunction "A_ANODE") (pintype "passive"))
      (node (ref "U1") (pin "7") (pinfunction "PB6(XTAL1/TOSC1)_7") (pintype "bidirectional"))
    )
    (net (code "27") (name "ROW4") (class "Default")
      (node (ref "U$12") (pin "ANODE") (pinfunction "A_ANODE") (pintype "passive"))
      (node (ref "U$20") (pin "ANODE") (pinfunction "A_ANODE") (pintype "passive"))
      (node (ref "U$28") (pin "ANODE") (pinfunction "A_ANODE") (pintype "passive"))
      (node (ref "U$36") (pin "ANODE") (pinfunction "A_ANODE") (pintype "passive"))
      (node (ref "U$4") (pin "ANODE") (pinfunction "A_ANODE") (pintype "passive"))
      (node (ref "U$44") (pin "ANODE") (pinfunction "A_ANODE") (pintype "passive"))
      (node (ref "U$52") (pin "ANODE") (pinfunction "A_ANODE") (pintype "passive"))
      (node (ref "U$60") (pin "ANODE") (pinfunction "A_ANODE") (pintype "passive"))
      (node (ref "U1") (pin "9") (pinfunction "PD5(T1)_9") (pintype "bidirectional"))
    )
    (net (code "28") (name "ROW5") (class "Default")
      (node (ref "U$13") (pin "ANODE") (pinfunction "A_ANODE") (pintype "passive"))
      (node (ref "U$21") (pin "ANODE") (pinfunction "A_ANODE") (pintype "passive"))
      (node (ref "U$29") (pin "ANODE") (pinfunction "A_ANODE") (pintype "passive"))
      (node (ref "U$37") (pin "ANODE") (pinfunction "A_ANODE") (pintype "passive"))
      (node (ref "U$45") (pin "ANODE") (pinfunction "A_ANODE") (pintype "passive"))
      (node (ref "U$5") (pin "ANODE") (pinfunction "A_ANODE") (pintype "passive"))
      (node (ref "U$53") (pin "ANODE") (pinfunction "A_ANODE") (pintype "passive"))
      (node (ref "U$61") (pin "ANODE") (pinfunction "A_ANODE") (pintype "passive"))
      (node (ref "U1") (pin "25") (pinfunction "PC2(ADC2)_25") (pintype "bidirectional"))
    )
    (net (code "29") (name "ROW6") (class "Default")
      (node (ref "U$14") (pin "ANODE") (pinfunction "A_ANODE") (pintype "passive"))
      (node (ref "U$22") (pin "ANODE") (pinfunction "A_ANODE") (pintype "passive"))
      (node (ref "U$30") (pin "ANODE") (pinfunction "A_ANODE") (pintype "passive"))
      (node (ref "U$38") (pin "ANODE") (pinfunction "A_ANODE") (pintype "passive"))
      (node (ref "U$46") (pin "ANODE") (pinfunction "A_ANODE") (pintype "passive"))
      (node (ref "U$54") (pin "ANODE") (pinfunction "A_ANODE") (pintype "passive"))
      (node (ref "U$6") (pin "ANODE") (pinfunction "A_ANODE") (pintype "passive"))
      (node (ref "U$62") (pin "ANODE") (pinfunction "A_ANODE") (pintype "passive"))
      (node (ref "U1") (pin "2") (pinfunction "PD4(XCK/T0)_2") (pintype "bidirectional"))
    )
    (net (code "30") (name "ROW7") (class "Default")
      (node (ref "U$15") (pin "ANODE") (pinfunction "A_ANODE") (pintype "passive"))
      (node (ref "U$23") (pin "ANODE") (pinfunction "A_ANODE") (pintype "passive"))
      (node (ref "U$31") (pin "ANODE") (pinfunction "A_ANODE") (pintype "passive"))
      (node (ref "U$39") (pin "ANODE") (pinfunction "A_ANODE") (pintype "passive"))
      (node (ref "U$47") (pin "ANODE") (pinfunction "A_ANODE") (pintype "passive"))
      (node (ref "U$55") (pin "ANODE") (pinfunction "A_ANODE") (pintype "passive"))
      (node (ref "U$63") (pin "ANODE") (pinfunction "A_ANODE") (pintype "passive"))
      (node (ref "U$7") (pin "ANODE") (pinfunction "A_ANODE") (pintype "passive"))
      (node (ref "U1") (pin "26") (pinfunction "PC3(ADC3)_26") (pintype "bidirectional"))
    )
    (net (code "31") (name "ROW8") (class "Default")
      (node (ref "U$16") (pin "ANODE") (pinfunction "A_ANODE") (pintype "passive"))
      (node (ref "U$24") (pin "ANODE") (pinfunction "A_ANODE") (pintype "passive"))
      (node (ref "U$32") (pin "ANODE") (pinfunction "A_ANODE") (pintype "passive"))
      (node (ref "U$40") (pin "ANODE") (pinfunction "A_ANODE") (pintype "passive"))
      (node (ref "U$48") (pin "ANODE") (pinfunction "A_ANODE") (pintype "passive"))
      (node (ref "U$56") (pin "ANODE") (pinfunction "A_ANODE") (pintype "passive"))
      (node (ref "U$64") (pin "ANODE") (pinfunction "A_ANODE") (pintype "passive"))
      (node (ref "U$8") (pin "ANODE") (pinfunction "A_ANODE") (pintype "passive"))
      (node (ref "U1") (pin "32") (pinfunction "PD2(INT0)_32") (pintype "bidirectional"))
    )
    (net (code "32") (name "SCK") (class "Default")
      (node (ref "J3") (pin "3") (pinfunction "3_3") (pintype "passive"))
      (node (ref "U1") (pin "17") (pinfunction "PB5(SCK)_17") (pintype "bidirectional"))
    )
    (net (code "33") (name "SCL") (class "Default")
      (node (ref "J1") (pin "3") (pinfunction "SCL_3") (pintype "input"))
      (node (ref "U1") (pin "28") (pinfunction "PC5(ADC5/SCL)_28") (pintype "bidirectional"))
    )
    (net (code "34") (name "SDA") (class "Default")
      (node (ref "J1") (pin "2") (pinfunction "SDA_2") (pintype "bidirectional"))
      (node (ref "U1") (pin "27") (pinfunction "PC4(ADC4/SDA)_27") (pintype "bidirectional"))
    )
    (net (code "35") (name "SWITCH") (class "Default")
      (node (ref "Q1") (pin "3") (pinfunction "D_3") (pintype "passive"))
      (node (ref "R12") (pin "1") (pinfunction "1_1") (pintype "passive"))
      (node (ref "S1") (pin "1") (pinfunction "1_1") (pintype "passive"))
      (node (ref "U1") (pin "11") (pinfunction "PD7(AIN1)_11") (pintype "bidirectional"))
    )
    (net (code "36") (name "V_USB") (class "Default")
      (node (ref "J2") (pin "1") (pinfunction "VUSB_1") (pintype "passive"))
      (node (ref "L1") (pin "1") (pinfunction "1_1") (pintype "passive"))
    )
    (net (code "37") (name "unconnected-(J1-NC-Pad4)") (class "Default")
      (node (ref "J1") (pin "4") (pinfunction "NC_4") (pintype "no_connect"))
    )
    (net (code "38") (name "unconnected-(J2-D--Pad2)") (class "Default")
      (node (ref "J2") (pin "2") (pinfunction "D-_2") (pintype "passive"))
    )
    (net (code "39") (name "unconnected-(J4-Pad1)") (class "Default")
      (node (ref "J4") (pin "1") (pinfunction "1_1") (pintype "passive"))
    )
    (net (code "40") (name "unconnected-(J4-Pad2)") (class "Default")
      (node (ref "J4") (pin "2") (pinfunction "2_2") (pintype "passive"))
    )
    (net (code "41") (name "unconnected-(J4-Pad3)") (class "Default")
      (node (ref "J4") (pin "3") (pinfunction "3_3") (pintype "passive"))
    )
    (net (code "42") (name "unconnected-(J4-Pad4)") (class "Default")
      (node (ref "J4") (pin "4") (pinfunction "4_4") (pintype "passive"))
    )
    (net (code "43") (name "unconnected-(J4-Pad5)") (class "Default")
      (node (ref "J4") (pin "5") (pinfunction "5_5") (pintype "passive"))
    )
    (net (code "44") (name "unconnected-(J4-Pad6)") (class "Default")
      (node (ref "J4") (pin "6") (pinfunction "6_6") (pintype "passive"))
    )
    (net (code "45") (name "unconnected-(J4-Pad7)") (class "Default")
      (node (ref "J4") (pin "7") (pinfunction "7_7") (pintype "passive"))
    )
    (net (code "46") (name "unconnected-(J4-Pad8)") (class "Default")
      (node (ref "J4") (pin "8") (pinfunction "8_8") (pintype "passive"))
    )
    (net (code "47") (name "unconnected-(J5-Pad1)") (class "Default")
      (node (ref "J5") (pin "1") (pinfunction "1_1") (pintype "passive"))
    )
    (net (code "48") (name "unconnected-(J5-Pad2)") (class "Default")
      (node (ref "J5") (pin "2") (pinfunction "2_2") (pintype "passive"))
    )
    (net (code "49") (name "unconnected-(J5-Pad3)") (class "Default")
      (node (ref "J5") (pin "3") (pinfunction "3_3") (pintype "passive"))
    )
    (net (code "50") (name "unconnected-(J5-Pad4)") (class "Default")
      (node (ref "J5") (pin "4") (pinfunction "4_4") (pintype "passive"))
    )
    (net (code "51") (name "unconnected-(J5-Pad5)") (class "Default")
      (node (ref "J5") (pin "5") (pinfunction "5_5") (pintype "passive"))
    )
    (net (code "52") (name "unconnected-(J5-Pad6)") (class "Default")
      (node (ref "J5") (pin "6") (pinfunction "6_6") (pintype "passive"))
    )
    (net (code "53") (name "unconnected-(J5-Pad7)") (class "Default")
      (node (ref "J5") (pin "7") (pinfunction "7_7") (pintype "passive"))
    )
    (net (code "54") (name "unconnected-(J5-Pad8)") (class "Default")
      (node (ref "J5") (pin "8") (pinfunction "8_8") (pintype "passive"))
    )
    (net (code "55") (name "unconnected-(J6-Pad1)") (class "Default")
      (node (ref "J6") (pin "1") (pinfunction "1_1") (pintype "passive"))
    )
    (net (code "56") (name "unconnected-(J6-Pad2)") (class "Default")
      (node (ref "J6") (pin "2") (pinfunction "2_2") (pintype "passive"))
    )
    (net (code "57") (name "unconnected-(J6-Pad3)") (class "Default")
      (node (ref "J6") (pin "3") (pinfunction "3_3") (pintype "passive"))
    )
    (net (code "58") (name "unconnected-(J6-Pad4)") (class "Default")
      (node (ref "J6") (pin "4") (pinfunction "4_4") (pintype "passive"))
    )
    (net (code "59") (name "unconnected-(J6-Pad5)") (class "Default")
      (node (ref "J6") (pin "5") (pinfunction "5_5") (pintype "passive"))
    )
    (net (code "60") (name "unconnected-(J6-Pad6)") (class "Default")
      (node (ref "J6") (pin "6") (pinfunction "6_6") (pintype "passive"))
    )
    (net (code "61") (name "unconnected-(J6-Pad7)") (class "Default")
      (node (ref "J6") (pin "7") (pinfunction "7_7") (pintype "passive"))
    )
    (net (code "62") (name "unconnected-(J6-Pad8)") (class "Default")
      (node (ref "J6") (pin "8") (pinfunction "8_8") (pintype "passive"))
    )
    (net (code "63") (name "unconnected-(J7-Pad1)") (class "Default")
      (node (ref "J7") (pin "1") (pinfunction "1_1") (pintype "passive"))
    )
    (net (code "64") (name "unconnected-(J7-Pad2)") (class "Default")
      (node (ref "J7") (pin "2") (pinfunction "2_2") (pintype "passive"))
    )
    (net (code "65") (name "unconnected-(J7-Pad3)") (class "Default")
      (node (ref "J7") (pin "3") (pinfunction "3_3") (pintype "passive"))
    )
    (net (code "66") (name "unconnected-(J7-Pad4)") (class "Default")
      (node (ref "J7") (pin "4") (pinfunction "4_4") (pintype "passive"))
    )
    (net (code "67") (name "unconnected-(J7-Pad5)") (class "Default")
      (node (ref "J7") (pin "5") (pinfunction "5_5") (pintype "passive"))
    )
    (net (code "68") (name "unconnected-(J7-Pad6)") (class "Default")
      (node (ref "J7") (pin "6") (pinfunction "6_6") (pintype "passive"))
    )
    (net (code "69") (name "unconnected-(J7-Pad7)") (class "Default")
      (node (ref "J7") (pin "7") (pinfunction "7_7") (pintype "passive"))
    )
    (net (code "70") (name "unconnected-(J7-Pad8)") (class "Default")
      (node (ref "J7") (pin "8") (pinfunction "8_8") (pintype "passive"))
    )
    (net (code "71") (name "unconnected-(U1-ADC6-Pad19)") (class "Default")
      (node (ref "U1") (pin "19") (pinfunction "ADC6_19") (pintype "bidirectional"))
    )
    (net (code "72") (name "unconnected-(U1-ADC7-Pad22)") (class "Default")
      (node (ref "U1") (pin "22") (pinfunction "ADC7_22") (pintype "bidirectional"))
    )
    (net (code "73") (name "unconnected-(U1-AREF-Pad20)") (class "Default")
      (node (ref "U1") (pin "20") (pinfunction "AREF_20") (pintype "passive"))
    )
  )
)
